# cv06_dobes.net
KiCad netlist of a schematic drawn in EAGLE
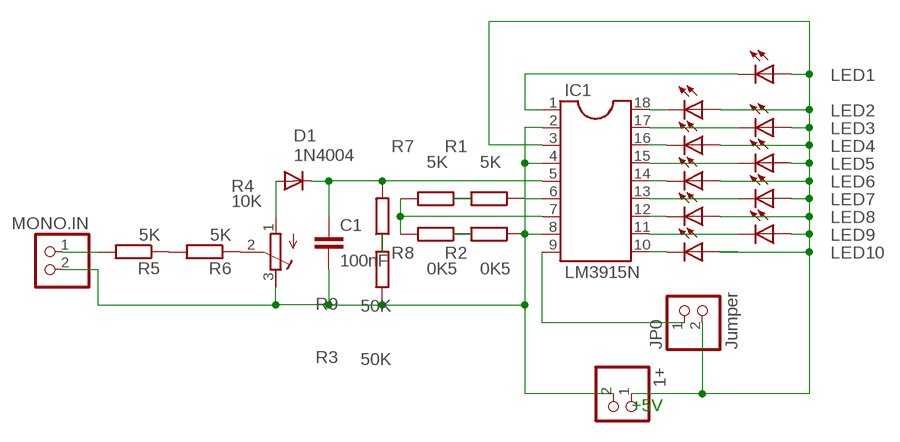
[diagram p0: schematic, sheet 1]

(export (version "E")
  (design (tool "Eeschema 10.0.6"))
  (components
    (comp (ref "1+")
      (value "PINHD-1X2")
      (footprint "eagle-import:1X02")
      (libsource (lib "eagle-import") (part "PINHD-1X2"))
    )
    (comp (ref "C1")
      (value "100nF")
      (footprint "eagle-import:C050-030X075")
      (libsource (lib "eagle-import") (part "C-EU050-030X075"))
    )
    (comp (ref "D1")
      (value "1N4004")
      (footprint "eagle-import:DO41-10")
      (libsource (lib "eagle-import") (part "1N4004"))
    )
    (comp (ref "IC1")
      (value "LM3915N")
      (footprint "eagle-import:SOCKET-18")
      (libsource (lib "eagle-import") (part "DIL18S"))
    )
    (comp (ref "JP0")
      (value "Jumper")
      (footprint "eagle-import:1X02")
      (libsource (lib "eagle-import") (part "PINHD-1X2"))
    )
    (comp (ref "LED1")
      (value "LED5MM")
      (footprint "eagle-import:LED5MM")
      (libsource (lib "eagle-import") (part "LED5MM"))
    )
    (comp (ref "LED2")
      (value "LED5MM")
      (footprint "eagle-import:LED5MM")
      (libsource (lib "eagle-import") (part "LED5MM"))
    )
    (comp (ref "LED3")
      (value "LED5MM")
      (footprint "eagle-import:LED5MM")
      (libsource (lib "eagle-import") (part "LED5MM"))
    )
    (comp (ref "LED4")
      (value "LED5MM")
      (footprint "eagle-import:LED5MM")
      (libsource (lib "eagle-import") (part "LED5MM"))
    )
    (comp (ref "LED5")
      (value "LED5MM")
      (footprint "eagle-import:LED5MM")
      (libsource (lib "eagle-import") (part "LED5MM"))
    )
    (comp (ref "LED6")
      (value "LED5MM")
      (footprint "eagle-import:LED5MM")
      (libsource (lib "eagle-import") (part "LED5MM"))
    )
    (comp (ref "LED7")
      (value "LED5MM")
      (footprint "eagle-import:LED5MM")
      (libsource (lib "eagle-import") (part "LED5MM"))
    )
    (comp (ref "LED8")
      (value "LED5MM")
      (footprint "eagle-import:LED5MM")
      (libsource (lib "eagle-import") (part "LED5MM"))
    )
    (comp (ref "LED9")
      (value "LED5MM")
      (footprint "eagle-import:LED5MM")
      (libsource (lib "eagle-import") (part "LED5MM"))
    )
    (comp (ref "LED10")
      (value "LED5MM")
      (footprint "eagle-import:LED5MM")
      (libsource (lib "eagle-import") (part "LED5MM"))
    )
    (comp (ref "MONO.IN")
      (value "PINHD-1X2")
      (footprint "eagle-import:1X02")
      (libsource (lib "eagle-import") (part "PINHD-1X2"))
    )
    (comp (ref "R1")
      (value "5K")
      (footprint "eagle-import:0207_7")
      (libsource (lib "eagle-import") (part "R-EU_0207/7"))
    )
    (comp (ref "R2")
      (value "0K5")
      (footprint "eagle-import:0207_7")
      (libsource (lib "eagle-import") (part "R-EU_0207/7"))
    )
    (comp (ref "R3")
      (value "50K")
      (footprint "eagle-import:0207_7")
      (libsource (lib "eagle-import") (part "R-EU_0207/7"))
    )
    (comp (ref "R4")
      (value "10K")
      (footprint "eagle-import:RTRIM64P")
      (libsource (lib "eagle-import") (part "R-TRIMM64P"))
    )
    (comp (ref "R5")
      (value "5K")
      (footprint "eagle-import:0207_7")
      (libsource (lib "eagle-import") (part "R-EU_0207/7"))
    )
    (comp (ref "R6")
      (value "5K")
      (footprint "eagle-import:0207_7")
      (libsource (lib "eagle-import") (part "R-EU_0207/7"))
    )
    (comp (ref "R7")
      (value "5K")
      (footprint "eagle-import:0207_7")
      (libsource (lib "eagle-import") (part "R-EU_0207/7"))
    )
    (comp (ref "R8")
      (value "0K5")
      (footprint "eagle-import:0207_7")
      (libsource (lib "eagle-import") (part "R-EU_0207/7"))
    )
    (comp (ref "R9")
      (value "50K")
      (footprint "eagle-import:0207_7")
      (libsource (lib "eagle-import") (part "R-EU_0207/7"))
    )
  )
  (nets
    (net (code "1") (name "Net-(1+-Pad1)") (class "Default")
      (node (ref "1+") (pin "1") (pinfunction "1_1") (pintype "passive"))
      (node (ref "IC1") (pin "3") (pinfunction "3_3") (pintype "passive"))
      (node (ref "JP0") (pin "2") (pinfunction "2_2") (pintype "passive"))
      (node (ref "LED1") (pin "A") (pinfunction "A_A") (pintype "passive"))
      (node (ref "LED10") (pin "A") (pinfunction "A_A") (pintype "passive"))
      (node (ref "LED2") (pin "A") (pinfunction "A_A") (pintype "passive"))
      (node (ref "LED3") (pin "A") (pinfunction "A_A") (pintype "passive"))
      (node (ref "LED4") (pin "A") (pinfunction "A_A") (pintype "passive"))
      (node (ref "LED5") (pin "A") (pinfunction "A_A") (pintype "passive"))
      (node (ref "LED6") (pin "A") (pinfunction "A_A") (pintype "passive"))
      (node (ref "LED7") (pin "A") (pinfunction "A_A") (pintype "passive"))
      (node (ref "LED8") (pin "A") (pinfunction "A_A") (pintype "passive"))
      (node (ref "LED9") (pin "A") (pinfunction "A_A") (pintype "passive"))
    )
    (net (code "2") (name "Net-(C1-Pad1)") (class "Default")
      (node (ref "C1") (pin "1") (pinfunction "1_1") (pintype "passive"))
      (node (ref "D1") (pin "C") (pinfunction "C_C") (pintype "passive"))
      (node (ref "IC1") (pin "5") (pinfunction "5_5") (pintype "passive"))
      (node (ref "R9") (pin "2") (pinfunction "2_2") (pintype "passive"))
    )
    (net (code "3") (name "Net-(IC1-Pad6)") (class "Default")
      (node (ref "IC1") (pin "6") (pinfunction "6_6") (pintype "passive"))
      (node (ref "R1") (pin "1") (pinfunction "1_1") (pintype "passive"))
    )
    (net (code "4") (name "Net-(IC1-Pad7)") (class "Default")
      (node (ref "IC1") (pin "7") (pinfunction "7_7") (pintype "passive"))
      (node (ref "R7") (pin "2") (pinfunction "2_2") (pintype "passive"))
      (node (ref "R8") (pin "2") (pinfunction "2_2") (pintype "passive"))
    )
    (net (code "5") (name "Net-(IC1-Pad9)") (class "Default")
      (node (ref "IC1") (pin "9") (pinfunction "9_9") (pintype "passive"))
      (node (ref "JP0") (pin "1") (pinfunction "1_1") (pintype "passive"))
    )
    (net (code "6") (name "Net-(LED1-C)") (class "Default")
      (node (ref "IC1") (pin "1") (pinfunction "1_1") (pintype "passive"))
      (node (ref "LED1") (pin "K") (pinfunction "C_K") (pintype "passive"))
    )
    (net (code "7") (name "Net-(LED2-C)") (class "Default")
      (node (ref "IC1") (pin "18") (pinfunction "18_18") (pintype "passive"))
      (node (ref "LED2") (pin "K") (pinfunction "C_K") (pintype "passive"))
    )
    (net (code "8") (name "Net-(LED3-C)") (class "Default")
      (node (ref "IC1") (pin "17") (pinfunction "17_17") (pintype "passive"))
      (node (ref "LED3") (pin "K") (pinfunction "C_K") (pintype "passive"))
    )
    (net (code "9") (name "Net-(LED4-C)") (class "Default")
      (node (ref "IC1") (pin "16") (pinfunction "16_16") (pintype "passive"))
      (node (ref "LED4") (pin "K") (pinfunction "C_K") (pintype "passive"))
    )
    (net (code "10") (name "Net-(LED5-C)") (class "Default")
      (node (ref "IC1") (pin "15") (pinfunction "15_15") (pintype "passive"))
      (node (ref "LED5") (pin "K") (pinfunction "C_K") (pintype "passive"))
    )
    (net (code "11") (name "Net-(LED6-C)") (class "Default")
      (node (ref "IC1") (pin "14") (pinfunction "14_14") (pintype "passive"))
      (node (ref "LED6") (pin "K") (pinfunction "C_K") (pintype "passive"))
    )
    (net (code "12") (name "Net-(LED7-C)") (class "Default")
      (node (ref "IC1") (pin "13") (pinfunction "13_13") (pintype "passive"))
      (node (ref "LED7") (pin "K") (pinfunction "C_K") (pintype "passive"))
    )
    (net (code "13") (name "Net-(LED8-C)") (class "Default")
      (node (ref "IC1") (pin "12") (pinfunction "12_12") (pintype "passive"))
      (node (ref "LED8") (pin "K") (pinfunction "C_K") (pintype "passive"))
    )
    (net (code "14") (name "Net-(LED9-C)") (class "Default")
      (node (ref "IC1") (pin "11") (pinfunction "11_11") (pintype "passive"))
      (node (ref "LED9") (pin "K") (pinfunction "C_K") (pintype "passive"))
    )
    (net (code "15") (name "Net-(LED10-C)") (class "Default")
      (node (ref "IC1") (pin "10") (pinfunction "10_10") (pintype "passive"))
      (node (ref "LED10") (pin "K") (pinfunction "C_K") (pintype "passive"))
    )
    (net (code "16") (name "Net-(MONO.IN-Pad1)") (class "Default")
      (node (ref "MONO.IN") (pin "1") (pinfunction "1_1") (pintype "passive"))
      (node (ref "R5") (pin "2") (pinfunction "2_2") (pintype "passive"))
    )
    (net (code "17") (name "Net-(R1-Pad2)") (class "Default")
      (node (ref "R1") (pin "2") (pinfunction "2_2") (pintype "passive"))
      (node (ref "R7") (pin "1") (pinfunction "1_1") (pintype "passive"))
    )
    (net (code "18") (name "Net-(R2-Pad2)") (class "Default")
      (node (ref "R2") (pin "2") (pinfunction "2_2") (pintype "passive"))
      (node (ref "R8") (pin "1") (pinfunction "1_1") (pintype "passive"))
    )
    (net (code "19") (name "Net-(R3-Pad2)") (class "Default")
      (node (ref "R3") (pin "2") (pinfunction "2_2") (pintype "passive"))
      (node (ref "R9") (pin "1") (pinfunction "1_1") (pintype "passive"))
    )
    (net (code "20") (name "Net-(R4-A)") (class "Default")
      (node (ref "1+") (pin "2") (pinfunction "2_2") (pintype "passive"))
      (node (ref "C1") (pin "2") (pinfunction "2_2") (pintype "passive"))
      (node (ref "IC1") (pin "2") (pinfunction "2_2") (pintype "passive"))
      (node (ref "IC1") (pin "4") (pinfunction "4_4") (pintype "passive"))
      (node (ref "IC1") (pin "8") (pinfunction "8_8") (pintype "passive"))
      (node (ref "MONO.IN") (pin "2") (pinfunction "2_2") (pintype "passive"))
      (node (ref "R2") (pin "1") (pinfunction "1_1") (pintype "passive"))
      (node (ref "R3") (pin "1") (pinfunction "1_1") (pintype "passive"))
      (node (ref "R4") (pin "3") (pinfunction "A_3") (pintype "passive"))
    )
    (net (code "21") (name "Net-(R4-E)") (class "Default")
      (node (ref "D1") (pin "A") (pinfunction "A_A") (pintype "passive"))
      (node (ref "R4") (pin "1") (pinfunction "E_1") (pintype "passive"))
    )
    (net (code "22") (name "Net-(R4-S)") (class "Default")
      (node (ref "R4") (pin "2") (pinfunction "S_2") (pintype "passive"))
      (node (ref "R6") (pin "1") (pinfunction "1_1") (pintype "passive"))
    )
    (net (code "23") (name "Net-(R5-Pad1)") (class "Default")
      (node (ref "R5") (pin "1") (pinfunction "1_1") (pintype "passive"))
      (node (ref "R6") (pin "2") (pinfunction "2_2") (pintype "passive"))
    )
  )
)
